# controller.net
KiCad netlist of a schematic drawn in EAGLE
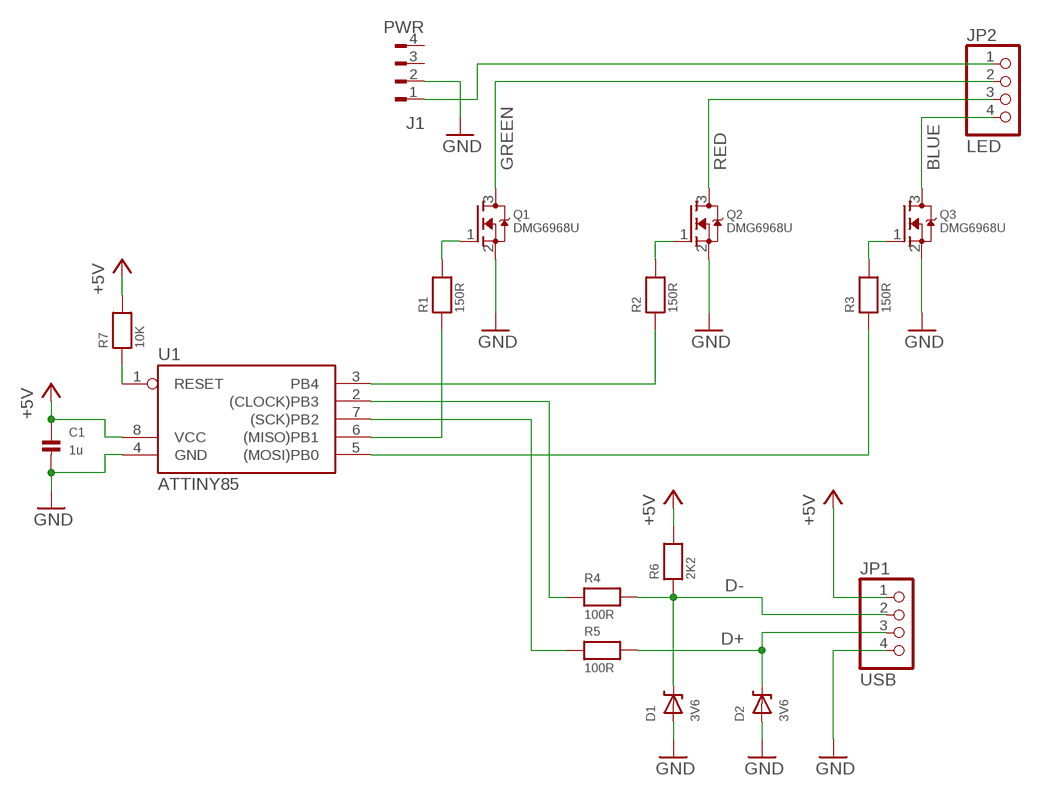
[diagram p0: schematic, sheet 1]

(export (version "E")
  (design (tool "Eeschema 10.0.6"))
  (components
    (comp (ref "C1")
      (value "1u")
      (footprint "eagle-import:0805")
      (libsource (lib "eagle-import") (part "CAP_CERAMIC0805"))
    )
    (comp (ref "D1")
      (value "3V6")
      (footprint "eagle-import:SOD-323")
      (libsource (lib "eagle-import") (part "DIODE-ZENERSOD-323"))
    )
    (comp (ref "D2")
      (value "3V6")
      (footprint "eagle-import:SOD-323")
      (libsource (lib "eagle-import") (part "DIODE-ZENERSOD-323"))
    )
    (comp (ref "J1")
      (value "PWR")
      (footprint "eagle-import:827001")
      (libsource (lib "eagle-import") (part "FLOP-4W827001"))
    )
    (comp (ref "JP1")
      (value "USB")
      (footprint "eagle-import:1X04")
      (libsource (lib "eagle-import") (part "PINHD-1X4"))
    )
    (comp (ref "JP2")
      (value "LED")
      (footprint "eagle-import:1X04")
      (libsource (lib "eagle-import") (part "PINHD-1X4"))
    )
    (comp (ref "Q1")
      (value "DMG6968U")
      (footprint "eagle-import:SOT23-W")
      (libsource (lib "eagle-import") (part "MOSFET-NWAVE"))
    )
    (comp (ref "Q2")
      (value "DMG6968U")
      (footprint "eagle-import:SOT23-W")
      (libsource (lib "eagle-import") (part "MOSFET-NWAVE"))
    )
    (comp (ref "Q3")
      (value "DMG6968U")
      (footprint "eagle-import:SOT23-W")
      (libsource (lib "eagle-import") (part "MOSFET-NWAVE"))
    )
    (comp (ref "R1")
      (value "150R")
      (footprint "eagle-import:0805")
      (libsource (lib "eagle-import") (part "RESISTOR0805"))
    )
    (comp (ref "R2")
      (value "150R")
      (footprint "eagle-import:0805")
      (libsource (lib "eagle-import") (part "RESISTOR0805"))
    )
    (comp (ref "R3")
      (value "150R")
      (footprint "eagle-import:0805")
      (libsource (lib "eagle-import") (part "RESISTOR0805"))
    )
    (comp (ref "R4")
      (value "100R")
      (footprint "eagle-import:0805")
      (libsource (lib "eagle-import") (part "RESISTOR0805"))
    )
    (comp (ref "R5")
      (value "100R")
      (footprint "eagle-import:0805")
      (libsource (lib "eagle-import") (part "RESISTOR0805"))
    )
    (comp (ref "R6")
      (value "2K2")
      (footprint "eagle-import:0805")
      (libsource (lib "eagle-import") (part "RESISTOR0805"))
    )
    (comp (ref "R7")
      (value "10K")
      (footprint "eagle-import:0805")
      (libsource (lib "eagle-import") (part "RESISTOR0805"))
    )
    (comp (ref "U1")
      (value "ATTINY85")
      (footprint "eagle-import:SOIC127P798X216-8N")
      (libsource (lib "eagle-import") (part "ATTINY85208MIL"))
    )
  )
  (nets
    (net (code "1") (name "+5V") (class "Default")
      (node (ref "C1") (pin "1") (pinfunction "P$1_1") (pintype "passive"))
      (node (ref "JP1") (pin "1") (pinfunction "1_1") (pintype "passive"))
      (node (ref "R6") (pin "2") (pinfunction "2_2") (pintype "passive"))
      (node (ref "R7") (pin "2") (pinfunction "2_2") (pintype "passive"))
      (node (ref "U1") (pin "8") (pinfunction "VCC_8") (pintype "power_in"))
    )
    (net (code "2") (name "/BLUE") (class "Default")
      (node (ref "JP2") (pin "4") (pinfunction "4_4") (pintype "passive"))
      (node (ref "Q3") (pin "3") (pinfunction "D_3") (pintype "bidirectional"))
    )
    (net (code "3") (name "/D+") (class "Default")
      (node (ref "D2") (pin "C") (pinfunction "C_C") (pintype "passive"))
      (node (ref "JP1") (pin "3") (pinfunction "3_3") (pintype "passive"))
      (node (ref "R5") (pin "2") (pinfunction "2_2") (pintype "passive"))
    )
    (net (code "4") (name "/D-") (class "Default")
      (node (ref "D1") (pin "C") (pinfunction "C_C") (pintype "passive"))
      (node (ref "JP1") (pin "2") (pinfunction "2_2") (pintype "passive"))
      (node (ref "R4") (pin "2") (pinfunction "2_2") (pintype "passive"))
      (node (ref "R6") (pin "1") (pinfunction "1_1") (pintype "passive"))
    )
    (net (code "5") (name "/GREEN") (class "Default")
      (node (ref "JP2") (pin "2") (pinfunction "2_2") (pintype "passive"))
      (node (ref "Q1") (pin "3") (pinfunction "D_3") (pintype "bidirectional"))
    )
    (net (code "6") (name "/RED") (class "Default")
      (node (ref "JP2") (pin "3") (pinfunction "3_3") (pintype "passive"))
      (node (ref "Q2") (pin "3") (pinfunction "D_3") (pintype "bidirectional"))
    )
    (net (code "7") (name "GND") (class "Default")
      (node (ref "C1") (pin "2") (pinfunction "P$2_2") (pintype "passive"))
      (node (ref "D1") (pin "A") (pinfunction "A_A") (pintype "passive"))
      (node (ref "D2") (pin "A") (pinfunction "A_A") (pintype "passive"))
      (node (ref "J1") (pin "2") (pinfunction "2_2") (pintype "passive"))
      (node (ref "JP1") (pin "4") (pinfunction "4_4") (pintype "passive"))
      (node (ref "Q1") (pin "2") (pinfunction "S_2") (pintype "bidirectional"))
      (node (ref "Q2") (pin "2") (pinfunction "S_2") (pintype "bidirectional"))
      (node (ref "Q3") (pin "2") (pinfunction "S_2") (pintype "bidirectional"))
      (node (ref "U1") (pin "4") (pinfunction "GND_4") (pintype "power_in"))
    )
    (net (code "8") (name "Net-(J1-Pad1)") (class "Default")
      (node (ref "J1") (pin "1") (pinfunction "1_1") (pintype "passive"))
      (node (ref "JP2") (pin "1") (pinfunction "1_1") (pintype "passive"))
    )
    (net (code "9") (name "Net-(Q1-G)") (class "Default")
      (node (ref "Q1") (pin "1") (pinfunction "G_1") (pintype "bidirectional"))
      (node (ref "R1") (pin "2") (pinfunction "2_2") (pintype "passive"))
    )
    (net (code "10") (name "Net-(Q2-G)") (class "Default")
      (node (ref "Q2") (pin "1") (pinfunction "G_1") (pintype "bidirectional"))
      (node (ref "R2") (pin "2") (pinfunction "2_2") (pintype "passive"))
    )
    (net (code "11") (name "Net-(Q3-G)") (class "Default")
      (node (ref "Q3") (pin "1") (pinfunction "G_1") (pintype "bidirectional"))
      (node (ref "R3") (pin "2") (pinfunction "2_2") (pintype "passive"))
    )
    (net (code "12") (name "Net-(U1-(CLOCK)PB3)") (class "Default")
      (node (ref "R4") (pin "1") (pinfunction "1_1") (pintype "passive"))
      (node (ref "U1") (pin "2") (pinfunction "(CLOCK)PB3_2") (pintype "bidirectional"))
    )
    (net (code "13") (name "Net-(U1-(MISO)PB1)") (class "Default")
      (node (ref "R1") (pin "1") (pinfunction "1_1") (pintype "passive"))
      (node (ref "U1") (pin "6") (pinfunction "(MISO)PB1_6") (pintype "bidirectional"))
    )
    (net (code "14") (name "Net-(U1-(MOSI)PB0)") (class "Default")
      (node (ref "R3") (pin "1") (pinfunction "1_1") (pintype "passive"))
      (node (ref "U1") (pin "5") (pinfunction "(MOSI)PB0_5") (pintype "bidirectional"))
    )
    (net (code "15") (name "Net-(U1-(SCK)PB2)") (class "Default")
      (node (ref "R5") (pin "1") (pinfunction "1_1") (pintype "passive"))
      (node (ref "U1") (pin "7") (pinfunction "(SCK)PB2_7") (pintype "bidirectional"))
    )
    (net (code "16") (name "Net-(U1-PB4)") (class "Default")
      (node (ref "R2") (pin "1") (pinfunction "1_1") (pintype "passive"))
      (node (ref "U1") (pin "3") (pinfunction "PB4_3") (pintype "bidirectional"))
    )
    (net (code "17") (name "Net-(U1-RESET)") (class "Default")
      (node (ref "R7") (pin "1") (pinfunction "1_1") (pintype "passive"))
      (node (ref "U1") (pin "1") (pinfunction "RESET_1") (pintype "input"))
    )
    (net (code "18") (name "unconnected-(J1-Pad3)") (class "Default")
      (node (ref "J1") (pin "3") (pinfunction "3_3") (pintype "passive"))
    )
    (net (code "19") (name "unconnected-(J1-Pad4)") (class "Default")
      (node (ref "J1") (pin "4") (pinfunction "4_4") (pintype "passive"))
    )
  )
)
